# snowflake.net
KiCad netlist of a schematic drawn in EAGLE
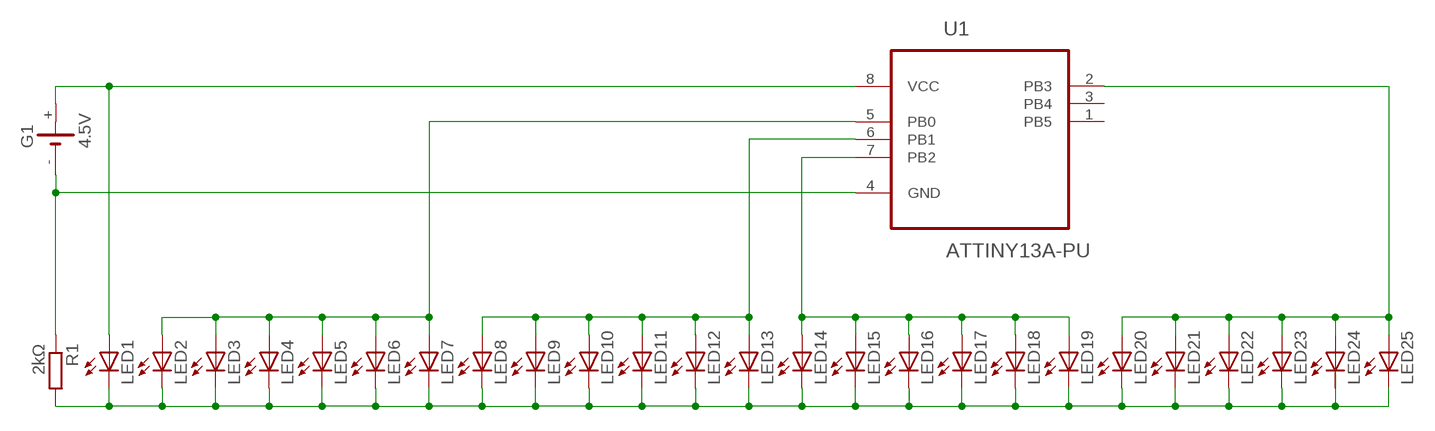
[diagram p0: schematic, sheet 1]

(export (version "E")
  (design (tool "Eeschema 10.0.6"))
  (components
    (comp (ref "G1")
      (value "4.5V")
      (footprint "eagle-import:CH291-1220LF")
      (libsource (lib "eagle-import") (part "CH291-1220LF"))
    )
    (comp (ref "LED1")
      (value "LED3MM")
      (footprint "eagle-import:LED3MM")
      (libsource (lib "eagle-import") (part "LED3MM"))
    )
    (comp (ref "LED2")
      (value "LED3MM")
      (footprint "eagle-import:LED3MM")
      (libsource (lib "eagle-import") (part "LED3MM"))
    )
    (comp (ref "LED3")
      (value "LED3MM")
      (footprint "eagle-import:LED3MM")
      (libsource (lib "eagle-import") (part "LED3MM"))
    )
    (comp (ref "LED4")
      (value "LED3MM")
      (footprint "eagle-import:LED3MM")
      (libsource (lib "eagle-import") (part "LED3MM"))
    )
    (comp (ref "LED5")
      (value "LED3MM")
      (footprint "eagle-import:LED3MM")
      (libsource (lib "eagle-import") (part "LED3MM"))
    )
    (comp (ref "LED6")
      (value "LED3MM")
      (footprint "eagle-import:LED3MM")
      (libsource (lib "eagle-import") (part "LED3MM"))
    )
    (comp (ref "LED7")
      (value "LED3MM")
      (footprint "eagle-import:LED3MM")
      (libsource (lib "eagle-import") (part "LED3MM"))
    )
    (comp (ref "LED8")
      (value "LED3MM")
      (footprint "eagle-import:LED3MM")
      (libsource (lib "eagle-import") (part "LED3MM"))
    )
    (comp (ref "LED9")
      (value "LED3MM")
      (footprint "eagle-import:LED3MM")
      (libsource (lib "eagle-import") (part "LED3MM"))
    )
    (comp (ref "LED10")
      (value "LED3MM")
      (footprint "eagle-import:LED3MM")
      (libsource (lib "eagle-import") (part "LED3MM"))
    )
    (comp (ref "LED11")
      (value "LED3MM")
      (footprint "eagle-import:LED3MM")
      (libsource (lib "eagle-import") (part "LED3MM"))
    )
    (comp (ref "LED12")
      (value "LED3MM")
      (footprint "eagle-import:LED3MM")
      (libsource (lib "eagle-import") (part "LED3MM"))
    )
    (comp (ref "LED13")
      (value "LED3MM")
      (footprint "eagle-import:LED3MM")
      (libsource (lib "eagle-import") (part "LED3MM"))
    )
    (comp (ref "LED14")
      (value "LED3MM")
      (footprint "eagle-import:LED3MM")
      (libsource (lib "eagle-import") (part "LED3MM"))
    )
    (comp (ref "LED15")
      (value "LED3MM")
      (footprint "eagle-import:LED3MM")
      (libsource (lib "eagle-import") (part "LED3MM"))
    )
    (comp (ref "LED16")
      (value "LED3MM")
      (footprint "eagle-import:LED3MM")
      (libsource (lib "eagle-import") (part "LED3MM"))
    )
    (comp (ref "LED17")
      (value "LED3MM")
      (footprint "eagle-import:LED3MM")
      (libsource (lib "eagle-import") (part "LED3MM"))
    )
    (comp (ref "LED18")
      (value "LED3MM")
      (footprint "eagle-import:LED3MM")
      (libsource (lib "eagle-import") (part "LED3MM"))
    )
    (comp (ref "LED19")
      (value "LED3MM")
      (footprint "eagle-import:LED3MM")
      (libsource (lib "eagle-import") (part "LED3MM"))
    )
    (comp (ref "LED20")
      (value "LED3MM")
      (footprint "eagle-import:LED3MM")
      (libsource (lib "eagle-import") (part "LED3MM"))
    )
    (comp (ref "LED21")
      (value "LED3MM")
      (footprint "eagle-import:LED3MM")
      (libsource (lib "eagle-import") (part "LED3MM"))
    )
    (comp (ref "LED22")
      (value "LED3MM")
      (footprint "eagle-import:LED3MM")
      (libsource (lib "eagle-import") (part "LED3MM"))
    )
    (comp (ref "LED23")
      (value "LED3MM")
      (footprint "eagle-import:LED3MM")
      (libsource (lib "eagle-import") (part "LED3MM"))
    )
    (comp (ref "LED24")
      (value "LED3MM")
      (footprint "eagle-import:LED3MM")
      (libsource (lib "eagle-import") (part "LED3MM"))
    )
    (comp (ref "LED25")
      (value "LED3MM")
      (footprint "eagle-import:LED3MM")
      (libsource (lib "eagle-import") (part "LED3MM"))
    )
    (comp (ref "R1")
      (value "2kΩ")
      (footprint "eagle-import:0204_5")
      (libsource (lib "eagle-import") (part "R-EU_0204/5"))
    )
    (comp (ref "U1")
      (value "ATTINY13A-PU")
      (footprint "eagle-import:DIP254P762X533-8")
      (libsource (lib "eagle-import") (part "ATTINY13A-PU"))
    )
  )
  (nets
    (net (code "1") (name "Net-(LED1-C)") (class "Default")
      (node (ref "LED1") (pin "K") (pinfunction "C_K") (pintype "passive"))
      (node (ref "LED10") (pin "K") (pinfunction "C_K") (pintype "passive"))
      (node (ref "LED11") (pin "K") (pinfunction "C_K") (pintype "passive"))
      (node (ref "LED12") (pin "K") (pinfunction "C_K") (pintype "passive"))
      (node (ref "LED13") (pin "K") (pinfunction "C_K") (pintype "passive"))
      (node (ref "LED14") (pin "K") (pinfunction "C_K") (pintype "passive"))
      (node (ref "LED15") (pin "K") (pinfunction "C_K") (pintype "passive"))
      (node (ref "LED16") (pin "K") (pinfunction "C_K") (pintype "passive"))
      (node (ref "LED17") (pin "K") (pinfunction "C_K") (pintype "passive"))
      (node (ref "LED18") (pin "K") (pinfunction "C_K") (pintype "passive"))
      (node (ref "LED19") (pin "K") (pinfunction "C_K") (pintype "passive"))
      (node (ref "LED2") (pin "K") (pinfunction "C_K") (pintype "passive"))
      (node (ref "LED20") (pin "K") (pinfunction "C_K") (pintype "passive"))
      (node (ref "LED21") (pin "K") (pinfunction "C_K") (pintype "passive"))
      (node (ref "LED22") (pin "K") (pinfunction "C_K") (pintype "passive"))
      (node (ref "LED23") (pin "K") (pinfunction "C_K") (pintype "passive"))
      (node (ref "LED25") (pin "K") (pinfunction "C_K") (pintype "passive"))
      (node (ref "LED3") (pin "K") (pinfunction "C_K") (pintype "passive"))
      (node (ref "LED4") (pin "K") (pinfunction "C_K") (pintype "passive"))
      (node (ref "LED5") (pin "K") (pinfunction "C_K") (pintype "passive"))
      (node (ref "LED6") (pin "K") (pinfunction "C_K") (pintype "passive"))
      (node (ref "LED7") (pin "K") (pinfunction "C_K") (pintype "passive"))
      (node (ref "LED8") (pin "K") (pinfunction "C_K") (pintype "passive"))
      (node (ref "LED9") (pin "K") (pinfunction "C_K") (pintype "passive"))
      (node (ref "R1") (pin "2") (pinfunction "2_2") (pintype "passive"))
    )
    (net (code "2") (name "Net-(U1-GND)") (class "Default")
      (node (ref "G1") (pin "-") (pinfunction "-_-") (pintype "passive"))
      (node (ref "R1") (pin "1") (pinfunction "1_1") (pintype "passive"))
      (node (ref "U1") (pin "4") (pinfunction "GND_4") (pintype "passive"))
    )
    (net (code "3") (name "Net-(U1-PB0)") (class "Default")
      (node (ref "LED2") (pin "A") (pinfunction "A_A") (pintype "passive"))
      (node (ref "LED3") (pin "A") (pinfunction "A_A") (pintype "passive"))
      (node (ref "LED4") (pin "A") (pinfunction "A_A") (pintype "passive"))
      (node (ref "LED5") (pin "A") (pinfunction "A_A") (pintype "passive"))
      (node (ref "LED6") (pin "A") (pinfunction "A_A") (pintype "passive"))
      (node (ref "LED7") (pin "A") (pinfunction "A_A") (pintype "passive"))
      (node (ref "U1") (pin "5") (pinfunction "PB0_5") (pintype "bidirectional"))
    )
    (net (code "4") (name "Net-(U1-PB1)") (class "Default")
      (node (ref "LED10") (pin "A") (pinfunction "A_A") (pintype "passive"))
      (node (ref "LED11") (pin "A") (pinfunction "A_A") (pintype "passive"))
      (node (ref "LED12") (pin "A") (pinfunction "A_A") (pintype "passive"))
      (node (ref "LED13") (pin "A") (pinfunction "A_A") (pintype "passive"))
      (node (ref "LED8") (pin "A") (pinfunction "A_A") (pintype "passive"))
      (node (ref "LED9") (pin "A") (pinfunction "A_A") (pintype "passive"))
      (node (ref "U1") (pin "6") (pinfunction "PB1_6") (pintype "bidirectional"))
    )
    (net (code "5") (name "Net-(U1-PB2)") (class "Default")
      (node (ref "LED14") (pin "A") (pinfunction "A_A") (pintype "passive"))
      (node (ref "LED15") (pin "A") (pinfunction "A_A") (pintype "passive"))
      (node (ref "LED16") (pin "A") (pinfunction "A_A") (pintype "passive"))
      (node (ref "LED17") (pin "A") (pinfunction "A_A") (pintype "passive"))
      (node (ref "LED18") (pin "A") (pinfunction "A_A") (pintype "passive"))
      (node (ref "LED19") (pin "A") (pinfunction "A_A") (pintype "passive"))
      (node (ref "U1") (pin "7") (pinfunction "PB2_7") (pintype "bidirectional"))
    )
    (net (code "6") (name "Net-(U1-PB3)") (class "Default")
      (node (ref "LED20") (pin "A") (pinfunction "A_A") (pintype "passive"))
      (node (ref "LED21") (pin "A") (pinfunction "A_A") (pintype "passive"))
      (node (ref "LED22") (pin "A") (pinfunction "A_A") (pintype "passive"))
      (node (ref "LED23") (pin "A") (pinfunction "A_A") (pintype "passive"))
      (node (ref "LED24") (pin "A") (pinfunction "A_A") (pintype "passive"))
      (node (ref "LED25") (pin "A") (pinfunction "A_A") (pintype "passive"))
      (node (ref "U1") (pin "2") (pinfunction "PB3_2") (pintype "bidirectional"))
    )
    (net (code "7") (name "Net-(U1-VCC)") (class "Default")
      (node (ref "G1") (pin "+") (pinfunction "+_+") (pintype "passive"))
      (node (ref "LED1") (pin "A") (pinfunction "A_A") (pintype "passive"))
      (node (ref "U1") (pin "8") (pinfunction "VCC_8") (pintype "power_in"))
    )
    (net (code "8") (name "unconnected-(LED24-C-PadK)") (class "Default")
      (node (ref "LED24") (pin "K") (pinfunction "C_K") (pintype "passive"))
    )
    (net (code "9") (name "unconnected-(U1-PB4-Pad3)") (class "Default")
      (node (ref "U1") (pin "3") (pinfunction "PB4_3") (pintype "bidirectional"))
    )
    (net (code "10") (name "unconnected-(U1-PB5-Pad1)") (class "Default")
      (node (ref "U1") (pin "1") (pinfunction "PB5_1") (pintype "bidirectional"))
    )
  )
)
